# supply.net
KiCad netlist of a schematic drawn in Altium Designer
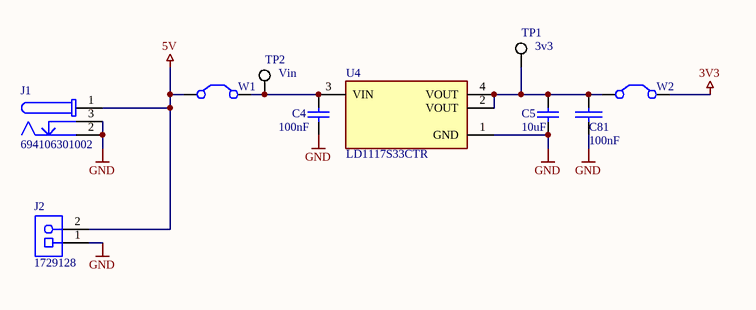
[diagram p0: supply.SchDoc]

(export (version "E")
  (design (tool "Eeschema 10.0.6"))
  (components
    (comp (ref "C4")
      (value "100nF")
      (footprint "Cap_0805")
      (description "Capacitor")
      (fields (field (name "PUBLISHER") "Altium Limited"))
      (libsource (lib "Miscellaneous Devices") (part "Cap"))
    )
    (comp (ref "C5")
      (value "10uF")
      (footprint "Cap_0805")
      (description "Capacitor")
      (fields (field (name "PUBLISHER") "Altium Limited"))
      (libsource (lib "Miscellaneous Devices") (part "Cap"))
    )
    (comp (ref "C81") (value "100nF") (footprint "Cap_0805") (libsource (lib "*") (part "C")))
    (comp (ref "J1")
      (value "694106301002")
      (footprint "694106301002")
      (libsource (lib "Altium Content Vault") (part "DC Power Jack"))
    )
    (comp (ref "J2")
      (value "1729128")
      (footprint "PHOE-1729128-2_V")
      (description "PCB Terminal Block, 13.5 A, 400 V, 2-Pin THD, RoHS, Bulk")
      (fields (field (name "MANUFACTURER") "Phoenix Contact"))
      (libsource (lib "Altium Content Vault") (part "CN-2P-F-R2"))
    )
    (comp (ref "TP1")
      (value "3v3")
      (footprint "KSTN-5019_V")
      (description "Test Point, 1 Position SMD, RoHS, Tape and Reel")
      (libsource (lib "Altium Content Vault") (part "TESTPOINT_WHITE"))
    )
    (comp (ref "TP2")
      (value "Vin")
      (footprint "KSTN-5019_V")
      (description "Test Point, 1 Position SMD, RoHS, Tape and Reel")
      (libsource (lib "Altium Content Vault") (part "TESTPOINT_WHITE"))
    )
    (comp (ref "U4")
      (value "LD1117S33CTR")
      (footprint "FP-SOT-223-0046067_14-MFG")
      (description "IC REG LINEAR 3.3V 800MA SOT223")
      (libsource (lib "Altium Content Vault") (part "7818869c5c16ceab15634627166a29d"))
    )
    (comp (ref "W1")
      (value "Jumper")
      (footprint "JUMPER")
      (description "Jumper Wire")
      (fields (field (name "PUBLISHER") "Altium Limited"))
      (libsource (lib "Miscellaneous Devices") (part "Jumper"))
    )
    (comp (ref "W2")
      (value "Jumper")
      (footprint "JUMPER")
      (description "Jumper Wire")
      (fields (field (name "PUBLISHER") "Altium Limited"))
      (libsource (lib "Miscellaneous Devices") (part "Jumper"))
    )
  )
  (nets
    (net (code "1") (name "3V3") (class "Default")
      (node (ref "W2") (pin "2") (pinfunction "C2_2") (pintype "passive"))
    )
    (net (code "2") (name "5V") (class "Default")
      (node (ref "J1") (pin "1") (pinfunction "1_1") (pintype "passive"))
      (node (ref "J2") (pin "2") (pinfunction "2_2") (pintype "passive"))
      (node (ref "W1") (pin "1") (pinfunction "C1_1") (pintype "passive"))
    )
    (net (code "3") (name "GND") (class "Default")
      (node (ref "C4") (pin "1") (pinfunction "1_1") (pintype "passive"))
      (node (ref "C5") (pin "1") (pinfunction "1_1") (pintype "passive"))
      (node (ref "C81") (pin "2") (pinfunction "2_2") (pintype "passive"))
      (node (ref "J1") (pin "2") (pinfunction "2_2") (pintype "passive"))
      (node (ref "J1") (pin "3") (pinfunction "3_3") (pintype "passive"))
      (node (ref "J2") (pin "1") (pinfunction "1_1") (pintype "passive"))
      (node (ref "U4") (pin "1") (pinfunction "GND_1") (pintype "power_in"))
    )
    (net (code "4") (name "Net-(U4-VIN)") (class "Default")
      (node (ref "C4") (pin "2") (pinfunction "2_2") (pintype "passive"))
      (node (ref "TP2") (pin "1") (pinfunction "1_1") (pintype "passive"))
      (node (ref "U4") (pin "3") (pinfunction "VIN_3") (pintype "power_in"))
      (node (ref "W1") (pin "2") (pinfunction "C2_2") (pintype "passive"))
    )
    (net (code "5") (name "Net-(W2-C1)") (class "Default")
      (node (ref "C5") (pin "2") (pinfunction "2_2") (pintype "passive"))
      (node (ref "C81") (pin "1") (pinfunction "1_1") (pintype "passive"))
      (node (ref "TP1") (pin "1") (pinfunction "1_1") (pintype "passive"))
      (node (ref "U4") (pin "2") (pinfunction "VOUT_2") (pintype "power_in"))
      (node (ref "U4") (pin "4") (pinfunction "VOUT_4") (pintype "power_in"))
      (node (ref "W2") (pin "1") (pinfunction "C1_1") (pintype "passive"))
    )
  )
)
